# driver_board_one_module_pic.net
KiCad netlist of a schematic drawn in EAGLE
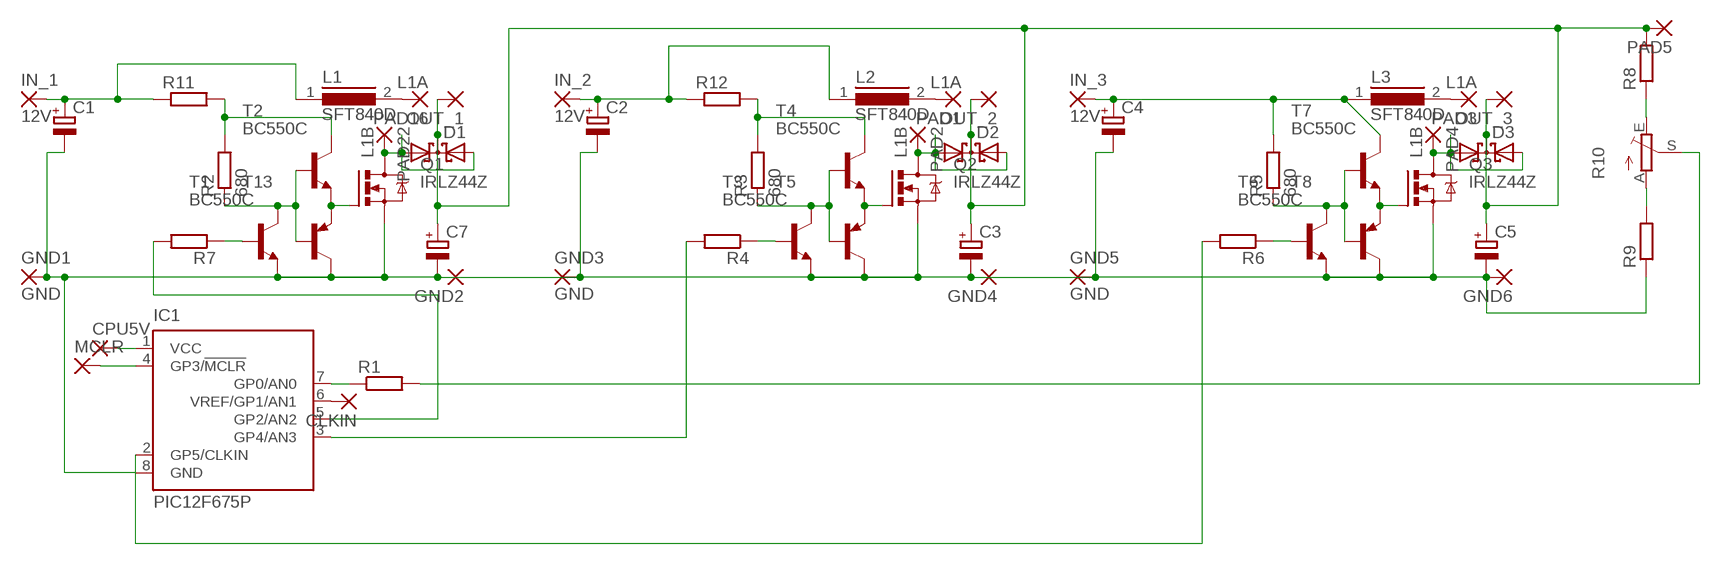
[diagram p0: schematic, sheet 1]

(export (version "E")
  (design (tool "Eeschema 10.0.6"))
  (components
    (comp (ref "C1")
      (value "CPOL-EUE5-8.5")
      (footprint "eagle-import:E5-8,5")
      (libsource (lib "eagle-import") (part "CPOL-EUE5-8.5"))
    )
    (comp (ref "C2")
      (value "CPOL-EUE5-8.5")
      (footprint "eagle-import:E5-8,5")
      (libsource (lib "eagle-import") (part "CPOL-EUE5-8.5"))
    )
    (comp (ref "C3")
      (value "CPOL-EUE5-8.5")
      (footprint "eagle-import:E5-8,5")
      (libsource (lib "eagle-import") (part "CPOL-EUE5-8.5"))
    )
    (comp (ref "C4")
      (value "CPOL-EUE5-8.5")
      (footprint "eagle-import:E5-8,5")
      (libsource (lib "eagle-import") (part "CPOL-EUE5-8.5"))
    )
    (comp (ref "C5")
      (value "CPOL-EUE5-8.5")
      (footprint "eagle-import:E5-8,5")
      (libsource (lib "eagle-import") (part "CPOL-EUE5-8.5"))
    )
    (comp (ref "C7")
      (value "CPOL-EUE5-8.5")
      (footprint "eagle-import:E5-8,5")
      (libsource (lib "eagle-import") (part "CPOL-EUE5-8.5"))
    )
    (comp (ref "CLKIN")
      (value "2,54/0,8")
      (footprint "eagle-import:2,54_0,8")
      (libsource (lib "eagle-import") (part "2,54/0,8"))
    )
    (comp (ref "CPU5V")
      (value "2,54/0,8")
      (footprint "eagle-import:2,54_0,8")
      (libsource (lib "eagle-import") (part "2,54/0,8"))
    )
    (comp (ref "D1")
      (value "DIODE_2SCHOTTKY-SOT93V")
      (footprint "eagle-import:SOT93S")
      (libsource (lib "eagle-import") (part "DIODE_2SCHOTTKY-SOT93V"))
    )
    (comp (ref "D2")
      (value "DIODE_2SCHOTTKY-SOT93V")
      (footprint "eagle-import:SOT93S")
      (libsource (lib "eagle-import") (part "DIODE_2SCHOTTKY-SOT93V"))
    )
    (comp (ref "D3")
      (value "DIODE_2SCHOTTKY-SOT93V")
      (footprint "eagle-import:SOT93S")
      (libsource (lib "eagle-import") (part "DIODE_2SCHOTTKY-SOT93V"))
    )
    (comp (ref "GND1")
      (value "GND")
      (footprint "eagle-import:3,81_1,3")
      (libsource (lib "eagle-import") (part "3,81/1,3"))
    )
    (comp (ref "GND2")
      (value "3,81/1,3")
      (footprint "eagle-import:3,81_1,3")
      (libsource (lib "eagle-import") (part "3,81/1,3"))
    )
    (comp (ref "GND3")
      (value "GND")
      (footprint "eagle-import:3,81_1,3")
      (libsource (lib "eagle-import") (part "3,81/1,3"))
    )
    (comp (ref "GND4")
      (value "3,81/1,3")
      (footprint "eagle-import:3,81_1,3")
      (libsource (lib "eagle-import") (part "3,81/1,3"))
    )
    (comp (ref "GND5")
      (value "GND")
      (footprint "eagle-import:3,81_1,3")
      (libsource (lib "eagle-import") (part "3,81/1,3"))
    )
    (comp (ref "GND6")
      (value "3,81/1,3")
      (footprint "eagle-import:3,81_1,3")
      (libsource (lib "eagle-import") (part "3,81/1,3"))
    )
    (comp (ref "IC1")
      (value "PIC12F675P")
      (footprint "eagle-import:DIL8")
      (fields (field (name "MF") "MICROCHIP") (field (name "MPN") "PIC12F675-E/P"))
      (libsource (lib "eagle-import") (part "PIC12F675P"))
    )
    (comp (ref "IN_1")
      (value "12V")
      (footprint "eagle-import:3,81_1,3")
      (libsource (lib "eagle-import") (part "3,81/1,3"))
    )
    (comp (ref "IN_2")
      (value "12V")
      (footprint "eagle-import:3,81_1,3")
      (libsource (lib "eagle-import") (part "3,81/1,3"))
    )
    (comp (ref "IN_3")
      (value "12V")
      (footprint "eagle-import:3,81_1,3")
      (libsource (lib "eagle-import") (part "3,81/1,3"))
    )
    (comp (ref "L1")
      (value "SFT840D")
      (footprint "eagle-import:SFT840D")
      (libsource (lib "eagle-import") (part "SFT840D"))
    )
    (comp (ref "L2")
      (value "SFT840D")
      (footprint "eagle-import:SFT840D")
      (libsource (lib "eagle-import") (part "SFT840D"))
    )
    (comp (ref "L3")
      (value "SFT840D")
      (footprint "eagle-import:SFT840D")
      (libsource (lib "eagle-import") (part "SFT840D"))
    )
    (comp (ref "MCLR")
      (value "2,54/0,8")
      (footprint "eagle-import:2,54_0,8")
      (libsource (lib "eagle-import") (part "2,54/0,8"))
    )
    (comp (ref "OUT_1")
      (value "3,81/1,3")
      (footprint "eagle-import:3,81_1,3")
      (libsource (lib "eagle-import") (part "3,81/1,3"))
    )
    (comp (ref "OUT_2")
      (value "3,81/1,3")
      (footprint "eagle-import:3,81_1,3")
      (libsource (lib "eagle-import") (part "3,81/1,3"))
    )
    (comp (ref "OUT_3")
      (value "3,81/1,3")
      (footprint "eagle-import:3,81_1,3")
      (libsource (lib "eagle-import") (part "3,81/1,3"))
    )
    (comp (ref "PAD1")
      (value "L1A")
      (footprint "eagle-import:3,81_1,1")
      (libsource (lib "eagle-import") (part "3,81/1,1"))
    )
    (comp (ref "PAD2")
      (value "L1B")
      (footprint "eagle-import:3,81_1,1")
      (libsource (lib "eagle-import") (part "3,81/1,1"))
    )
    (comp (ref "PAD3")
      (value "L1A")
      (footprint "eagle-import:3,81_1,1")
      (libsource (lib "eagle-import") (part "3,81/1,1"))
    )
    (comp (ref "PAD4")
      (value "L1B")
      (footprint "eagle-import:3,81_1,1")
      (libsource (lib "eagle-import") (part "3,81/1,1"))
    )
    (comp (ref "PAD5")
      (value "3,81/1,3")
      (footprint "eagle-import:3,81_1,3")
      (libsource (lib "eagle-import") (part "3,81/1,3"))
    )
    (comp (ref "PAD16")
      (value "L1A")
      (footprint "eagle-import:3,81_1,1")
      (libsource (lib "eagle-import") (part "3,81/1,1"))
    )
    (comp (ref "PAD22")
      (value "L1B")
      (footprint "eagle-import:3,81_1,1")
      (libsource (lib "eagle-import") (part "3,81/1,1"))
    )
    (comp (ref "Q1")
      (value "IRLZ44Z")
      (footprint "eagle-import:TO220BH")
      (libsource (lib "eagle-import") (part "IRLZ44Z"))
    )
    (comp (ref "Q2")
      (value "IRLZ44Z")
      (footprint "eagle-import:TO220BH")
      (libsource (lib "eagle-import") (part "IRLZ44Z"))
    )
    (comp (ref "Q3")
      (value "IRLZ44Z")
      (footprint "eagle-import:TO220BH")
      (libsource (lib "eagle-import") (part "IRLZ44Z"))
    )
    (comp (ref "R1")
      (value "R-EU_0207/7")
      (footprint "eagle-import:0207_7")
      (libsource (lib "eagle-import") (part "resistor_R-EU_0207/7"))
    )
    (comp (ref "R2")
      (value "680")
      (footprint "eagle-import:0204_7")
      (libsource (lib "eagle-import") (part "resistor_R-EU_0204/7"))
    )
    (comp (ref "R3")
      (value "680")
      (footprint "eagle-import:0204_7")
      (libsource (lib "eagle-import") (part "resistor_R-EU_0204/7"))
    )
    (comp (ref "R4")
      (value "R-EU_0207/10")
      (footprint "eagle-import:0207_10")
      (libsource (lib "eagle-import") (part "R-EU_0207/10"))
    )
    (comp (ref "R5")
      (value "680")
      (footprint "eagle-import:0204_7")
      (libsource (lib "eagle-import") (part "resistor_R-EU_0204/7"))
    )
    (comp (ref "R6")
      (value "R-EU_0207/7")
      (footprint "eagle-import:0207_7")
      (libsource (lib "eagle-import") (part "resistor_R-EU_0207/7"))
    )
    (comp (ref "R7")
      (value "R-EU_0207/7")
      (footprint "eagle-import:0207_7")
      (libsource (lib "eagle-import") (part "resistor_R-EU_0207/7"))
    )
    (comp (ref "R8")
      (value "R-EU_0207/7")
      (footprint "eagle-import:0207_7")
      (libsource (lib "eagle-import") (part "resistor_R-EU_0207/7"))
    )
    (comp (ref "R9")
      (value "R-EU_0207/7")
      (footprint "eagle-import:0207_7")
      (libsource (lib "eagle-import") (part "resistor_R-EU_0207/7"))
    )
    (comp (ref "R10")
      (value "TRIM_EU-RJ9W")
      (footprint "eagle-import:RJ9W")
      (libsource (lib "eagle-import") (part "TRIM_EU-RJ9W"))
    )
    (comp (ref "R11")
      (value "R-EU_0207/10")
      (footprint "eagle-import:0207_10")
      (libsource (lib "eagle-import") (part "resistor_R-EU_0207/10"))
    )
    (comp (ref "R12")
      (value "R-EU_0207/15")
      (footprint "eagle-import:0207_15")
      (libsource (lib "eagle-import") (part "R-EU_0207/15"))
    )
    (comp (ref "T1")
      (value "BC550C")
      (footprint "eagle-import:TO92-EBC")
      (libsource (lib "eagle-import") (part "BC550C"))
    )
    (comp (ref "T2")
      (value "BC550C")
      (footprint "eagle-import:TO92-EBC")
      (libsource (lib "eagle-import") (part "BC550C"))
    )
    (comp (ref "T3")
      (value "BC550C")
      (footprint "eagle-import:TO92-EBC")
      (libsource (lib "eagle-import") (part "BC550C"))
    )
    (comp (ref "T4")
      (value "BC550C")
      (footprint "eagle-import:TO92-EBC")
      (libsource (lib "eagle-import") (part "BC550C"))
    )
    (comp (ref "T5")
      (value "BC557C-PNP-TO92-EBC")
      (footprint "eagle-import:TO92-EBC")
      (libsource (lib "eagle-import") (part "-PNP-TO92-EBCBC557C"))
    )
    (comp (ref "T6")
      (value "BC550C")
      (footprint "eagle-import:TO92-EBC")
      (libsource (lib "eagle-import") (part "BC550C"))
    )
    (comp (ref "T7")
      (value "BC550C")
      (footprint "eagle-import:TO92-EBC")
      (libsource (lib "eagle-import") (part "BC550C"))
    )
    (comp (ref "T8")
      (value "BC557C-PNP-TO92-EBC")
      (footprint "eagle-import:TO92-EBC")
      (libsource (lib "eagle-import") (part "-PNP-TO92-EBCBC557C"))
    )
    (comp (ref "T13")
      (value "BC557C-PNP-TO92-EBC")
      (footprint "eagle-import:TO92-EBC")
      (libsource (lib "eagle-import") (part "-PNP-TO92-EBCBC557C"))
    )
  )
  (nets
    (net (code "1") (name "Net-(CLKIN-P)") (class "Default")
      (node (ref "CLKIN") (pin "1") (pinfunction "P_1") (pintype "passive"))
      (node (ref "IC1") (pin "6") (pinfunction "VREF/GP1/AN1_6") (pintype "bidirectional"))
    )
    (net (code "2") (name "Net-(CPU5V-P)") (class "Default")
      (node (ref "CPU5V") (pin "1") (pinfunction "P_1") (pintype "passive"))
      (node (ref "IC1") (pin "1") (pinfunction "VCC_1") (pintype "power_in"))
    )
    (net (code "3") (name "Net-(GND1-P)") (class "Default")
      (node (ref "C1") (pin "-") (pinfunction "-_-") (pintype "passive"))
      (node (ref "C2") (pin "-") (pinfunction "-_-") (pintype "passive"))
      (node (ref "C3") (pin "-") (pinfunction "-_-") (pintype "passive"))
      (node (ref "C4") (pin "-") (pinfunction "-_-") (pintype "passive"))
      (node (ref "C5") (pin "-") (pinfunction "-_-") (pintype "passive"))
      (node (ref "C7") (pin "-") (pinfunction "-_-") (pintype "passive"))
      (node (ref "GND1") (pin "1") (pinfunction "P_1") (pintype "passive"))
      (node (ref "GND2") (pin "1") (pinfunction "P_1") (pintype "passive"))
      (node (ref "GND3") (pin "1") (pinfunction "P_1") (pintype "passive"))
      (node (ref "GND4") (pin "1") (pinfunction "P_1") (pintype "passive"))
      (node (ref "GND5") (pin "1") (pinfunction "P_1") (pintype "passive"))
      (node (ref "GND6") (pin "1") (pinfunction "P_1") (pintype "passive"))
      (node (ref "IC1") (pin "8") (pinfunction "GND_8") (pintype "power_in"))
      (node (ref "Q1") (pin "S") (pinfunction "S_S") (pintype "passive"))
      (node (ref "Q2") (pin "S") (pinfunction "S_S") (pintype "passive"))
      (node (ref "Q3") (pin "S") (pinfunction "S_S") (pintype "passive"))
      (node (ref "R9") (pin "1") (pinfunction "1_1") (pintype "passive"))
      (node (ref "T1") (pin "E") (pinfunction "E_E") (pintype "passive"))
      (node (ref "T13") (pin "C") (pinfunction "C_C") (pintype "passive"))
      (node (ref "T3") (pin "E") (pinfunction "E_E") (pintype "passive"))
      (node (ref "T5") (pin "C") (pinfunction "C_C") (pintype "passive"))
      (node (ref "T6") (pin "E") (pinfunction "E_E") (pintype "passive"))
      (node (ref "T8") (pin "C") (pinfunction "C_C") (pintype "passive"))
    )
    (net (code "4") (name "Net-(IC1-GP0{slash}AN0)") (class "Default")
      (node (ref "IC1") (pin "7") (pinfunction "GP0/AN0_7") (pintype "bidirectional"))
      (node (ref "R1") (pin "1") (pinfunction "1_1") (pintype "passive"))
    )
    (net (code "5") (name "Net-(IC1-GP2{slash}AN2)") (class "Default")
      (node (ref "IC1") (pin "5") (pinfunction "GP2/AN2_5") (pintype "bidirectional"))
      (node (ref "R7") (pin "2") (pinfunction "2_2") (pintype "passive"))
    )
    (net (code "6") (name "Net-(IC1-GP3{slash}~{MCLR})") (class "Default")
      (node (ref "IC1") (pin "4") (pinfunction "GP3/~{MCLR}_4") (pintype "input"))
      (node (ref "MCLR") (pin "1") (pinfunction "P_1") (pintype "passive"))
    )
    (net (code "7") (name "Net-(IC1-GP4{slash}AN3)") (class "Default")
      (node (ref "IC1") (pin "3") (pinfunction "GP4/AN3_3") (pintype "bidirectional"))
      (node (ref "R4") (pin "2") (pinfunction "2_2") (pintype "passive"))
    )
    (net (code "8") (name "Net-(IC1-GP5{slash}CLKIN)") (class "Default")
      (node (ref "IC1") (pin "2") (pinfunction "GP5/CLKIN_2") (pintype "bidirectional"))
      (node (ref "R6") (pin "2") (pinfunction "2_2") (pintype "passive"))
    )
    (net (code "9") (name "Net-(IN_1-P)") (class "Default")
      (node (ref "C1") (pin "+") (pinfunction "+_+") (pintype "passive"))
      (node (ref "IN_1") (pin "1") (pinfunction "P_1") (pintype "passive"))
      (node (ref "L1") (pin "1") (pinfunction "1_1") (pintype "passive"))
      (node (ref "R11") (pin "1") (pinfunction "1_1") (pintype "passive"))
    )
    (net (code "10") (name "Net-(IN_2-P)") (class "Default")
      (node (ref "C2") (pin "+") (pinfunction "+_+") (pintype "passive"))
      (node (ref "IN_2") (pin "1") (pinfunction "P_1") (pintype "passive"))
      (node (ref "L2") (pin "1") (pinfunction "1_1") (pintype "passive"))
      (node (ref "R12") (pin "1") (pinfunction "1_1") (pintype "passive"))
    )
    (net (code "11") (name "Net-(IN_3-P)") (class "Default")
      (node (ref "C4") (pin "+") (pinfunction "+_+") (pintype "passive"))
      (node (ref "IN_3") (pin "1") (pinfunction "P_1") (pintype "passive"))
      (node (ref "L3") (pin "1") (pinfunction "1_1") (pintype "passive"))
      (node (ref "R5") (pin "2") (pinfunction "2_2") (pintype "passive"))
      (node (ref "T7") (pin "C") (pinfunction "C_C") (pintype "passive"))
    )
    (net (code "12") (name "Net-(OUT_1-P)") (class "Default")
      (node (ref "C3") (pin "+") (pinfunction "+_+") (pintype "passive"))
      (node (ref "C5") (pin "+") (pinfunction "+_+") (pintype "passive"))
      (node (ref "C7") (pin "+") (pinfunction "+_+") (pintype "passive"))
      (node (ref "D1") (pin "C") (pinfunction "C_C") (pintype "passive"))
      (node (ref "D2") (pin "C") (pinfunction "C_C") (pintype "passive"))
      (node (ref "D3") (pin "C") (pinfunction "C_C") (pintype "passive"))
      (node (ref "OUT_1") (pin "1") (pinfunction "P_1") (pintype "passive"))
      (node (ref "OUT_2") (pin "1") (pinfunction "P_1") (pintype "passive"))
      (node (ref "OUT_3") (pin "1") (pinfunction "P_1") (pintype "passive"))
      (node (ref "PAD5") (pin "1") (pinfunction "P_1") (pintype "passive"))
      (node (ref "R8") (pin "2") (pinfunction "2_2") (pintype "passive"))
    )
    (net (code "13") (name "Net-(PAD1-P)") (class "Default")
      (node (ref "L2") (pin "2") (pinfunction "2_2") (pintype "passive"))
      (node (ref "PAD1") (pin "1") (pinfunction "P_1") (pintype "passive"))
    )
    (net (code "14") (name "Net-(PAD2-P)") (class "Default")
      (node (ref "D2") (pin "A1") (pinfunction "A1_A1") (pintype "passive"))
      (node (ref "D2") (pin "A2") (pinfunction "A2_A2") (pintype "passive"))
      (node (ref "PAD2") (pin "1") (pinfunction "P_1") (pintype "passive"))
      (node (ref "Q2") (pin "D") (pinfunction "D_D") (pintype "passive"))
    )
    (net (code "15") (name "Net-(PAD3-P)") (class "Default")
      (node (ref "L3") (pin "2") (pinfunction "2_2") (pintype "passive"))
      (node (ref "PAD3") (pin "1") (pinfunction "P_1") (pintype "passive"))
    )
    (net (code "16") (name "Net-(PAD4-P)") (class "Default")
      (node (ref "D3") (pin "A1") (pinfunction "A1_A1") (pintype "passive"))
      (node (ref "D3") (pin "A2") (pinfunction "A2_A2") (pintype "passive"))
      (node (ref "PAD4") (pin "1") (pinfunction "P_1") (pintype "passive"))
      (node (ref "Q3") (pin "D") (pinfunction "D_D") (pintype "passive"))
    )
    (net (code "17") (name "Net-(PAD16-P)") (class "Default")
      (node (ref "L1") (pin "2") (pinfunction "2_2") (pintype "passive"))
      (node (ref "PAD16") (pin "1") (pinfunction "P_1") (pintype "passive"))
    )
    (net (code "18") (name "Net-(PAD22-P)") (class "Default")
      (node (ref "D1") (pin "A1") (pinfunction "A1_A1") (pintype "passive"))
      (node (ref "D1") (pin "A2") (pinfunction "A2_A2") (pintype "passive"))
      (node (ref "PAD22") (pin "1") (pinfunction "P_1") (pintype "passive"))
      (node (ref "Q1") (pin "D") (pinfunction "D_D") (pintype "passive"))
    )
    (net (code "19") (name "Net-(Q1-PadG)") (class "Default")
      (node (ref "Q1") (pin "G") (pinfunction "G_G") (pintype "passive"))
      (node (ref "T13") (pin "E") (pinfunction "E_E") (pintype "passive"))
      (node (ref "T2") (pin "E") (pinfunction "E_E") (pintype "passive"))
    )
    (net (code "20") (name "Net-(Q2-PadG)") (class "Default")
      (node (ref "Q2") (pin "G") (pinfunction "G_G") (pintype "passive"))
      (node (ref "T4") (pin "E") (pinfunction "E_E") (pintype "passive"))
      (node (ref "T5") (pin "E") (pinfunction "E_E") (pintype "passive"))
    )
    (net (code "21") (name "Net-(Q3-PadG)") (class "Default")
      (node (ref "Q3") (pin "G") (pinfunction "G_G") (pintype "passive"))
      (node (ref "T7") (pin "E") (pinfunction "E_E") (pintype "passive"))
      (node (ref "T8") (pin "E") (pinfunction "E_E") (pintype "passive"))
    )
    (net (code "22") (name "Net-(R1-Pad2)") (class "Default")
      (node (ref "R1") (pin "2") (pinfunction "2_2") (pintype "passive"))
      (node (ref "R10") (pin "S") (pinfunction "S_S") (pintype "passive"))
    )
    (net (code "23") (name "Net-(R2-Pad1)") (class "Default")
      (node (ref "R2") (pin "1") (pinfunction "1_1") (pintype "passive"))
      (node (ref "T1") (pin "C") (pinfunction "C_C") (pintype "passive"))
      (node (ref "T13") (pin "B") (pinfunction "B_B") (pintype "passive"))
      (node (ref "T2") (pin "B") (pinfunction "B_B") (pintype "passive"))
    )
    (net (code "24") (name "Net-(R3-Pad1)") (class "Default")
      (node (ref "R3") (pin "1") (pinfunction "1_1") (pintype "passive"))
      (node (ref "T3") (pin "C") (pinfunction "C_C") (pintype "passive"))
      (node (ref "T4") (pin "B") (pinfunction "B_B") (pintype "passive"))
      (node (ref "T5") (pin "B") (pinfunction "B_B") (pintype "passive"))
    )
    (net (code "25") (name "Net-(R4-Pad1)") (class "Default")
      (node (ref "R4") (pin "1") (pinfunction "1_1") (pintype "passive"))
      (node (ref "T3") (pin "B") (pinfunction "B_B") (pintype "passive"))
    )
    (net (code "26") (name "Net-(R5-Pad1)") (class "Default")
      (node (ref "R5") (pin "1") (pinfunction "1_1") (pintype "passive"))
      (node (ref "T6") (pin "C") (pinfunction "C_C") (pintype "passive"))
      (node (ref "T7") (pin "B") (pinfunction "B_B") (pintype "passive"))
      (node (ref "T8") (pin "B") (pinfunction "B_B") (pintype "passive"))
    )
    (net (code "27") (name "Net-(R6-Pad1)") (class "Default")
      (node (ref "R6") (pin "1") (pinfunction "1_1") (pintype "passive"))
      (node (ref "T6") (pin "B") (pinfunction "B_B") (pintype "passive"))
    )
    (net (code "28") (name "Net-(R7-Pad1)") (class "Default")
      (node (ref "R7") (pin "1") (pinfunction "1_1") (pintype "passive"))
      (node (ref "T1") (pin "B") (pinfunction "B_B") (pintype "passive"))
    )
    (net (code "29") (name "Net-(R10-PadA)") (class "Default")
      (node (ref "R10") (pin "A") (pinfunction "A_A") (pintype "passive"))
      (node (ref "R9") (pin "2") (pinfunction "2_2") (pintype "passive"))
    )
    (net (code "30") (name "Net-(R10-PadE)") (class "Default")
      (node (ref "R10") (pin "E") (pinfunction "E_E") (pintype "passive"))
      (node (ref "R8") (pin "1") (pinfunction "1_1") (pintype "passive"))
    )
    (net (code "31") (name "Net-(R11-Pad2)") (class "Default")
      (node (ref "R11") (pin "2") (pinfunction "2_2") (pintype "passive"))
      (node (ref "R2") (pin "2") (pinfunction "2_2") (pintype "passive"))
      (node (ref "T2") (pin "C") (pinfunction "C_C") (pintype "passive"))
    )
    (net (code "32") (name "Net-(R12-Pad2)") (class "Default")
      (node (ref "R12") (pin "2") (pinfunction "2_2") (pintype "passive"))
      (node (ref "R3") (pin "2") (pinfunction "2_2") (pintype "passive"))
      (node (ref "T4") (pin "C") (pinfunction "C_C") (pintype "passive"))
    )
  )
)
